# schematic.net
KiCad netlist of a schematic drawn in Altium Designer
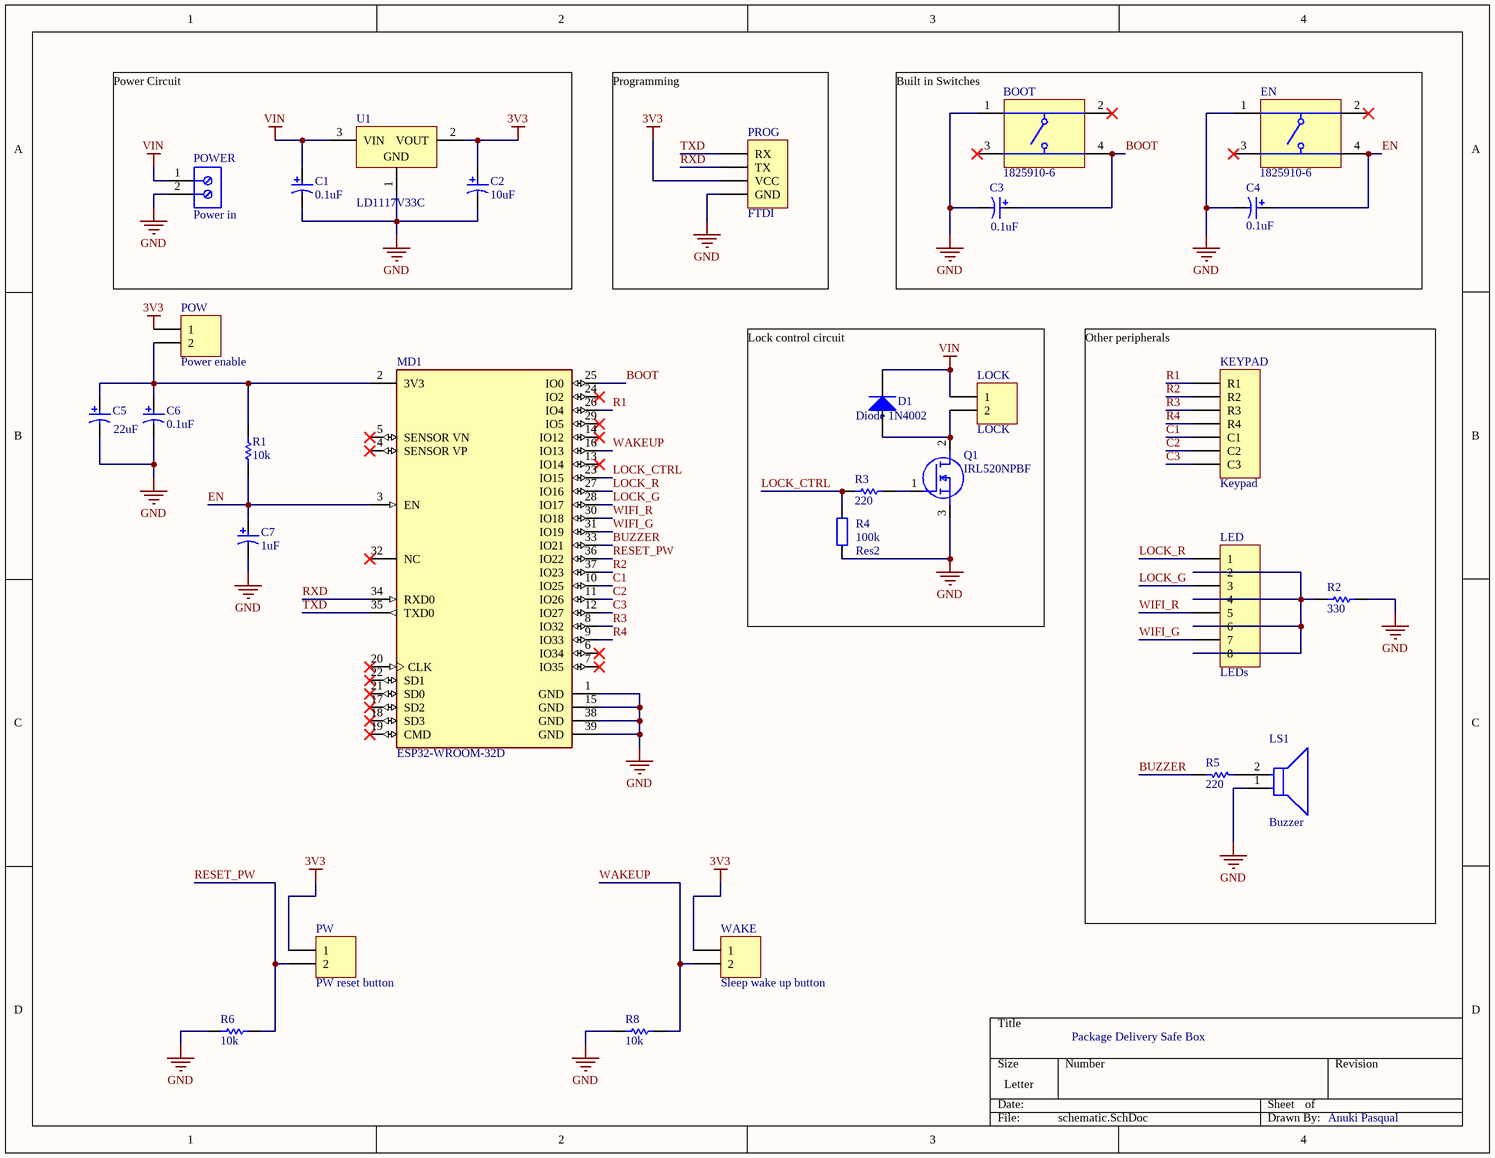
[diagram p0: schematic.SchDoc]

(export (version "E")
  (design (tool "Eeschema 10.0.6"))
  (components
    (comp (ref "BOOT")
      (value "1825910-6")
      (footprint "TECO-1825910-6_V")
      (description "Tact Switch, SPST-NO, 0.05 A, -35 to 85 degC, 4-Pin THD, RoHS, Bulk")
      (fields (field (name "MANUFACTURER") "TE Connectivity"))
      (libsource (lib "Altium Content Vault") (part "SW-SPST-4_A"))
    )
    (comp (ref "C1")
      (value "0.1uF")
      (footprint "CAPPR55-200-1100X500X1200")
      (description "Aluminum Electrolytic Capacitor, 22 uF, +/- 20%, 50 V, -40 to 85 degC, 2-Pin THD, RoHS, Bulk")
      (fields (field (name "VOLTAGE") "50V") (field (name "MANUFACTURER") "Panasonic"))
      (libsource (lib "Altium Content Vault") (part "CAP-P-2"))
    )
    (comp (ref "C2")
      (value "10uF")
      (footprint "CAPPR55-200-1100X500X1200")
      (description "Aluminum Electrolytic Capacitor, 22 uF, +/- 20%, 50 V, -40 to 85 degC, 2-Pin THD, RoHS, Bulk")
      (fields (field (name "VOLTAGE") "50V") (field (name "MANUFACTURER") "Panasonic"))
      (libsource (lib "Altium Content Vault") (part "CAP-P-2"))
    )
    (comp (ref "C3")
      (value "0.1uF")
      (footprint "CAPPR55-200-1100X500X1200")
      (description "Aluminum Electrolytic Capacitor, 22 uF, +/- 20%, 50 V, -40 to 85 degC, 2-Pin THD, RoHS, Bulk")
      (fields (field (name "VOLTAGE") "50V") (field (name "MANUFACTURER") "Panasonic"))
      (libsource (lib "Altium Content Vault") (part "CAP-P-2"))
    )
    (comp (ref "C4")
      (value "0.1uF")
      (footprint "CAPPR55-200-1100X500X1200")
      (description "Aluminum Electrolytic Capacitor, 22 uF, +/- 20%, 50 V, -40 to 85 degC, 2-Pin THD, RoHS, Bulk")
      (fields (field (name "VOLTAGE") "50V") (field (name "MANUFACTURER") "Panasonic"))
      (libsource (lib "Altium Content Vault") (part "CAP-P-2"))
    )
    (comp (ref "C5")
      (value "22uF")
      (footprint "CAPPR55-200-1100X500X1200")
      (description "Aluminum Electrolytic Capacitor, 22 uF, +/- 20%, 50 V, -40 to 85 degC, 2-Pin THD, RoHS, Bulk")
      (fields (field (name "VOLTAGE") "50V") (field (name "MANUFACTURER") "Panasonic"))
      (libsource (lib "Altium Content Vault") (part "CAP-P-2"))
    )
    (comp (ref "C6")
      (value "0.1uF")
      (footprint "CAPPR55-200-1100X500X1200")
      (description "Aluminum Electrolytic Capacitor, 22 uF, +/- 20%, 50 V, -40 to 85 degC, 2-Pin THD, RoHS, Bulk")
      (fields (field (name "VOLTAGE") "50V") (field (name "MANUFACTURER") "Panasonic"))
      (libsource (lib "Altium Content Vault") (part "CAP-P-2"))
    )
    (comp (ref "C7")
      (value "1uF")
      (footprint "CAPPR55-200-1100X500X1200")
      (description "Aluminum Electrolytic Capacitor, 22 uF, +/- 20%, 50 V, -40 to 85 degC, 2-Pin THD, RoHS, Bulk")
      (fields (field (name "VOLTAGE") "50V") (field (name "MANUFACTURER") "Panasonic"))
      (libsource (lib "Altium Content Vault") (part "CAP-P-2"))
    )
    (comp (ref "D1")
      (value "Diode 1N4002")
      (footprint "DO-41")
      (description "1 Amp General Purpose Rectifier")
      (fields (field (name "PUBLISHER") "Altium Limited"))
      (libsource (lib "Miscellaneous Devices") (part "Diode 1N4002"))
    )
    (comp (ref "EN")
      (value "1825910-6")
      (footprint "TECO-1825910-6_V")
      (description "Tact Switch, SPST-NO, 0.05 A, -35 to 85 degC, 4-Pin THD, RoHS, Bulk")
      (fields (field (name "MANUFACTURER") "TE Connectivity"))
      (libsource (lib "Altium Content Vault") (part "SW-SPST-4_A"))
    )
    (comp (ref "KEYPAD")
      (value "Keypad")
      (footprint "Miscellaneous Connectors:HDR1X7")
      (description "Header, 7-Pin")
      (fields (field (name "PUBLISHER") "Altium Limited"))
      (libsource (lib "Miscellaneous Connectors") (part "Header 7"))
    )
    (comp (ref "LED")
      (value "LEDs")
      (footprint "HDR1X8")
      (description "Header, 8-Pin")
      (fields (field (name "PUBLISHER") "Altium Limited"))
      (libsource (lib "Miscellaneous Connectors") (part "Header 8"))
    )
    (comp (ref "LOCK")
      (value "LOCK")
      (footprint "HDR1X2")
      (description "Header, 2-Pin")
      (fields (field (name "PUBLISHER") "Altium Limited"))
      (libsource (lib "Miscellaneous Connectors") (part "Header 2"))
    )
    (comp (ref "LS1")
      (value "Buzzer")
      (footprint "FP-MCKPX-G1203A-K4056-MFG")
      (description "MAGNETIC BUZZER AND TRANSDUCER - More Details")
      (fields
        (field (name "MANUFACTURER PART NUMBER") "MCKPX-G1203A-K4056")
        (field (name "MANUFACTURER") "Multicomp Pro")
      )
      (libsource (lib "Altium Content Vault") (part "1973c4b650225fd2ddacaff6b763965"))
    )
    (comp (ref "MD1")
      (value "ESP32-WROOM-32D")
      (footprint "FP-ESP32-WROOM-32D-MFG")
      (description "WIFI MODULE 32MBITS SPI FLASH")
      (fields
        (field (name "OCTOPART") "https://octopart.com/esp32-wroom-32d-espressif+systems-91040050")
        (field (name "MANUFACTURER") "Espressif Systems")
      )
      (libsource (lib "Altium Content Vault") (part "a031a76f8c27026a7a7f4657ff233a3"))
    )
    (comp (ref "POW")
      (value "Power enable")
      (footprint "HDR1X2")
      (description "Header, 2-Pin")
      (fields (field (name "PUBLISHER") "Altium Limited"))
      (libsource (lib "Miscellaneous Connectors") (part "Header 2"))
    )
    (comp (ref "POWER")
      (value "Power in")
      (footprint "691102710002")
      (description "Series 102 - 5.00 mm Horizontal Entry Modular with Pressure Clamp WR-TBL, 2 pin")
      (fields
        (field (name "MANUFACTURER") "Wurth Elektronik")
        (field (name "PART NUMBER") "691102710002")
        (field (name "PUBLISHER") "WurthElektronik")
      )
      (libsource (lib "Altium Content Vault") (part "WE-CN-1P-F-TB2"))
    )
    (comp (ref "PROG")
      (value "FTDI")
      (footprint "HDR1X4")
      (description "Header, 4-Pin")
      (fields (field (name "PUBLISHER") "Altium Limited"))
      (libsource (lib "Miscellaneous Connectors") (part "Header 4"))
    )
    (comp (ref "PW")
      (value "PW reset button")
      (footprint "HDR1X2")
      (description "Header, 2-Pin")
      (fields (field (name "PUBLISHER") "Altium Limited"))
      (libsource (lib "Miscellaneous Connectors") (part "Header 2"))
    )
    (comp (ref "Q1")
      (value "IRL520NPBF")
      (footprint "SamacSys:TO254P469X1042X1967-3P")
      (description "MOSFET (N-Channel)")
      (fields (field (name "MOUSER PART NUMBER") "942-IRL520NPBF"))
      (libsource (lib "SamacSys") (part "IRL520NPBF"))
    )
    (comp (ref "R1")
      (value "10k")
      (footprint "AXIAL-0.3")
      (description "Resistor")
      (fields (field (name "PUBLISHER") "Altium Limited"))
      (libsource (lib "Miscellaneous Devices") (part "Res1"))
    )
    (comp (ref "R2")
      (value "330")
      (footprint "AXIAL-0.3")
      (description "Resistor")
      (fields (field (name "PUBLISHER") "Altium Limited"))
      (libsource (lib "Miscellaneous Devices") (part "Res1"))
    )
    (comp (ref "R3")
      (value "220")
      (footprint "AXIAL-0.3")
      (description "Resistor")
      (fields (field (name "PUBLISHER") "Altium Limited"))
      (libsource (lib "Miscellaneous Devices") (part "Res1"))
    )
    (comp (ref "R4")
      (value "Res2")
      (footprint "AXIAL-0.4")
      (description "Resistor")
      (fields (field (name "ALTIUM_VALUE") "100k") (field (name "PUBLISHER") "Altium Limited"))
      (libsource (lib "Miscellaneous Devices") (part "Res2"))
    )
    (comp (ref "R5")
      (value "220")
      (footprint "AXIAL-0.3")
      (description "Resistor")
      (fields (field (name "PUBLISHER") "Altium Limited"))
      (libsource (lib "Miscellaneous Devices") (part "Res1"))
    )
    (comp (ref "R6")
      (value "10k")
      (footprint "AXIAL-0.3")
      (description "Resistor")
      (fields (field (name "PUBLISHER") "Altium Limited"))
      (libsource (lib "Miscellaneous Devices") (part "Res1"))
    )
    (comp (ref "R8")
      (value "10k")
      (footprint "AXIAL-0.3")
      (description "Resistor")
      (fields (field (name "PUBLISHER") "Altium Limited"))
      (libsource (lib "Miscellaneous Devices") (part "Res1"))
    )
    (comp (ref "U1")
      (value "LD1117V33C")
      (footprint "TO220")
      (description "Fixed Low Drop Positive Voltage Regulator, 3.3V, 3-Pin TO-220")
      (libsource (lib "Altium Content Vault") (part "PM-REG-LD1117V-SIL3"))
    )
    (comp (ref "WAKE")
      (value "Sleep wake up button")
      (footprint "HDR1X2")
      (description "Header, 2-Pin")
      (fields (field (name "PUBLISHER") "Altium Limited"))
      (libsource (lib "Miscellaneous Connectors") (part "Header 2"))
    )
  )
  (nets
    (net (code "1") (name "/BOOT") (class "Default")
      (node (ref "BOOT") (pin "4") (pinfunction "4_4") (pintype "passive"))
      (node (ref "C3") (pin "1") (pinfunction "1_1") (pintype "passive"))
      (node (ref "MD1") (pin "25") (pinfunction "IO0_25") (pintype "bidirectional"))
    )
    (net (code "2") (name "/BUZZER") (class "Default")
      (node (ref "MD1") (pin "33") (pinfunction "IO21_33") (pintype "bidirectional"))
      (node (ref "R5") (pin "1") (pinfunction "1_1") (pintype "passive"))
    )
    (net (code "3") (name "/C1") (class "Default")
      (node (ref "KEYPAD") (pin "5") (pinfunction "C1_5") (pintype "passive"))
      (node (ref "MD1") (pin "10") (pinfunction "IO25_10") (pintype "bidirectional"))
    )
    (net (code "4") (name "/C2") (class "Default")
      (node (ref "KEYPAD") (pin "6") (pinfunction "C2_6") (pintype "passive"))
      (node (ref "MD1") (pin "11") (pinfunction "IO26_11") (pintype "bidirectional"))
    )
    (net (code "5") (name "/C3") (class "Default")
      (node (ref "KEYPAD") (pin "7") (pinfunction "C3_7") (pintype "passive"))
      (node (ref "MD1") (pin "12") (pinfunction "IO27_12") (pintype "bidirectional"))
    )
    (net (code "6") (name "/EN") (class "Default")
      (node (ref "C4") (pin "1") (pinfunction "1_1") (pintype "passive"))
      (node (ref "C7") (pin "1") (pinfunction "1_1") (pintype "passive"))
      (node (ref "EN") (pin "4") (pinfunction "4_4") (pintype "passive"))
      (node (ref "MD1") (pin "3") (pinfunction "EN_3") (pintype "input"))
      (node (ref "R1") (pin "1") (pinfunction "1_1") (pintype "passive"))
    )
    (net (code "7") (name "/LOCK_CTRL") (class "Default")
      (node (ref "MD1") (pin "23") (pinfunction "IO15_23") (pintype "bidirectional"))
      (node (ref "R3") (pin "2") (pinfunction "2_2") (pintype "passive"))
      (node (ref "R4") (pin "2") (pinfunction "2_2") (pintype "passive"))
    )
    (net (code "8") (name "/LOCK_G") (class "Default")
      (node (ref "LED") (pin "3") (pinfunction "3_3") (pintype "passive"))
      (node (ref "MD1") (pin "28") (pinfunction "IO17_28") (pintype "bidirectional"))
    )
    (net (code "9") (name "/LOCK_R") (class "Default")
      (node (ref "LED") (pin "1") (pinfunction "1_1") (pintype "passive"))
      (node (ref "MD1") (pin "27") (pinfunction "IO16_27") (pintype "bidirectional"))
    )
    (net (code "10") (name "/R1") (class "Default")
      (node (ref "KEYPAD") (pin "1") (pinfunction "R1_1") (pintype "passive"))
      (node (ref "MD1") (pin "26") (pinfunction "IO4_26") (pintype "bidirectional"))
    )
    (net (code "11") (name "/R2") (class "Default")
      (node (ref "KEYPAD") (pin "2") (pinfunction "R2_2") (pintype "passive"))
      (node (ref "MD1") (pin "37") (pinfunction "IO23_37") (pintype "bidirectional"))
    )
    (net (code "12") (name "/R3") (class "Default")
      (node (ref "KEYPAD") (pin "3") (pinfunction "R3_3") (pintype "passive"))
      (node (ref "MD1") (pin "8") (pinfunction "IO32_8") (pintype "bidirectional"))
    )
    (net (code "13") (name "/R4") (class "Default")
      (node (ref "KEYPAD") (pin "4") (pinfunction "R4_4") (pintype "passive"))
      (node (ref "MD1") (pin "9") (pinfunction "IO33_9") (pintype "bidirectional"))
    )
    (net (code "14") (name "/RESET_PW") (class "Default")
      (node (ref "MD1") (pin "36") (pinfunction "IO22_36") (pintype "bidirectional"))
      (node (ref "PW") (pin "2") (pinfunction "2_2") (pintype "passive"))
      (node (ref "R6") (pin "1") (pinfunction "1_1") (pintype "passive"))
    )
    (net (code "15") (name "/RXD") (class "Default")
      (node (ref "MD1") (pin "34") (pinfunction "RXD0_34") (pintype "input"))
      (node (ref "PROG") (pin "2") (pinfunction "TX_2") (pintype "passive"))
    )
    (net (code "16") (name "/TXD") (class "Default")
      (node (ref "MD1") (pin "35") (pinfunction "TXD0_35") (pintype "output"))
      (node (ref "PROG") (pin "1") (pinfunction "RX_1") (pintype "passive"))
    )
    (net (code "17") (name "/WAKEUP") (class "Default")
      (node (ref "MD1") (pin "16") (pinfunction "IO13_16") (pintype "bidirectional"))
      (node (ref "R8") (pin "1") (pinfunction "1_1") (pintype "passive"))
      (node (ref "WAKE") (pin "2") (pinfunction "2_2") (pintype "passive"))
    )
    (net (code "18") (name "/WIFI_G") (class "Default")
      (node (ref "LED") (pin "7") (pinfunction "7_7") (pintype "passive"))
      (node (ref "MD1") (pin "31") (pinfunction "IO19_31") (pintype "bidirectional"))
    )
    (net (code "19") (name "/WIFI_R") (class "Default")
      (node (ref "LED") (pin "5") (pinfunction "5_5") (pintype "passive"))
      (node (ref "MD1") (pin "30") (pinfunction "IO18_30") (pintype "bidirectional"))
    )
    (net (code "20") (name "3V3") (class "Default")
      (node (ref "C2") (pin "1") (pinfunction "1_1") (pintype "passive"))
      (node (ref "POW") (pin "1") (pinfunction "1_1") (pintype "passive"))
      (node (ref "PROG") (pin "3") (pinfunction "VCC_3") (pintype "passive"))
      (node (ref "PW") (pin "1") (pinfunction "1_1") (pintype "passive"))
      (node (ref "U1") (pin "2") (pinfunction "VOUT_2") (pintype "power_in"))
      (node (ref "WAKE") (pin "1") (pinfunction "1_1") (pintype "passive"))
    )
    (net (code "21") (name "GND") (class "Default")
      (node (ref "BOOT") (pin "1") (pinfunction "1_1") (pintype "passive"))
      (node (ref "C1") (pin "2") (pinfunction "2_2") (pintype "passive"))
      (node (ref "C2") (pin "2") (pinfunction "2_2") (pintype "passive"))
      (node (ref "C3") (pin "2") (pinfunction "2_2") (pintype "passive"))
      (node (ref "C4") (pin "2") (pinfunction "2_2") (pintype "passive"))
      (node (ref "C5") (pin "2") (pinfunction "2_2") (pintype "passive"))
      (node (ref "C6") (pin "2") (pinfunction "2_2") (pintype "passive"))
      (node (ref "C7") (pin "2") (pinfunction "2_2") (pintype "passive"))
      (node (ref "EN") (pin "1") (pinfunction "1_1") (pintype "passive"))
      (node (ref "LS1") (pin "1") (pinfunction "C_1") (pintype "passive"))
      (node (ref "MD1") (pin "1") (pinfunction "GND_1") (pintype "power_in"))
      (node (ref "MD1") (pin "15") (pinfunction "GND_15") (pintype "power_in"))
      (node (ref "MD1") (pin "38") (pinfunction "GND_38") (pintype "power_in"))
      (node (ref "MD1") (pin "39") (pinfunction "GND_39") (pintype "power_in"))
      (node (ref "POWER") (pin "2") (pinfunction "2_2") (pintype "passive"))
      (node (ref "PROG") (pin "4") (pinfunction "GND_4") (pintype "passive"))
      (node (ref "Q1") (pin "3") (pinfunction "S_3") (pintype "passive"))
      (node (ref "R2") (pin "2") (pinfunction "2_2") (pintype "passive"))
      (node (ref "R4") (pin "1") (pinfunction "1_1") (pintype "passive"))
      (node (ref "R6") (pin "2") (pinfunction "2_2") (pintype "passive"))
      (node (ref "R8") (pin "2") (pinfunction "2_2") (pintype "passive"))
      (node (ref "U1") (pin "1") (pinfunction "GND_1") (pintype "power_in"))
    )
    (net (code "22") (name "Net-(D1-A)") (class "Default")
      (node (ref "D1") (pin "1") (pinfunction "A_1") (pintype "passive"))
      (node (ref "LOCK") (pin "2") (pinfunction "2_2") (pintype "passive"))
      (node (ref "Q1") (pin "2") (pinfunction "D_2") (pintype "passive"))
    )
    (net (code "23") (name "Net-(LED-Pad2)") (class "Default")
      (node (ref "LED") (pin "2") (pinfunction "2_2") (pintype "passive"))
      (node (ref "LED") (pin "4") (pinfunction "4_4") (pintype "passive"))
      (node (ref "LED") (pin "6") (pinfunction "6_6") (pintype "passive"))
      (node (ref "LED") (pin "8") (pinfunction "8_8") (pintype "passive"))
      (node (ref "R2") (pin "1") (pinfunction "1_1") (pintype "passive"))
    )
    (net (code "24") (name "Net-(LS1-A)") (class "Default")
      (node (ref "LS1") (pin "2") (pinfunction "A_2") (pintype "passive"))
      (node (ref "R5") (pin "2") (pinfunction "2_2") (pintype "passive"))
    )
    (net (code "25") (name "Net-(MD1-3V3)") (class "Default")
      (node (ref "C5") (pin "1") (pinfunction "1_1") (pintype "passive"))
      (node (ref "C6") (pin "1") (pinfunction "1_1") (pintype "passive"))
      (node (ref "MD1") (pin "2") (pinfunction "3V3_2") (pintype "power_in"))
      (node (ref "POW") (pin "2") (pinfunction "2_2") (pintype "passive"))
      (node (ref "R1") (pin "2") (pinfunction "2_2") (pintype "passive"))
    )
    (net (code "26") (name "Net-(Q1-G)") (class "Default")
      (node (ref "Q1") (pin "1") (pinfunction "G_1") (pintype "passive"))
      (node (ref "R3") (pin "1") (pinfunction "1_1") (pintype "passive"))
    )
    (net (code "27") (name "VIN") (class "Default")
      (node (ref "C1") (pin "1") (pinfunction "1_1") (pintype "passive"))
      (node (ref "D1") (pin "2") (pinfunction "K_2") (pintype "passive"))
      (node (ref "LOCK") (pin "1") (pinfunction "1_1") (pintype "passive"))
      (node (ref "POWER") (pin "1") (pinfunction "1_1") (pintype "passive"))
      (node (ref "U1") (pin "3") (pinfunction "VIN_3") (pintype "power_in"))
    )
    (net (code "28") (name "unconnected-(BOOT-Pad2)") (class "Default")
      (node (ref "BOOT") (pin "2") (pinfunction "2_2") (pintype "passive+no_connect"))
    )
    (net (code "29") (name "unconnected-(BOOT-Pad3)") (class "Default")
      (node (ref "BOOT") (pin "3") (pinfunction "3_3") (pintype "passive+no_connect"))
    )
    (net (code "30") (name "unconnected-(EN-Pad2)") (class "Default")
      (node (ref "EN") (pin "2") (pinfunction "2_2") (pintype "passive+no_connect"))
    )
    (net (code "31") (name "unconnected-(EN-Pad3)") (class "Default")
      (node (ref "EN") (pin "3") (pinfunction "3_3") (pintype "passive+no_connect"))
    )
    (net (code "32") (name "unconnected-(MD1-CLK-Pad20)") (class "Default")
      (node (ref "MD1") (pin "20") (pinfunction "CLK_20") (pintype "input+no_connect"))
    )
    (net (code "33") (name "unconnected-(MD1-CMD-Pad19)") (class "Default")
      (node (ref "MD1") (pin "19") (pinfunction "CMD_19") (pintype "bidirectional+no_connect"))
    )
    (net (code "34") (name "unconnected-(MD1-IO2-Pad24)") (class "Default")
      (node (ref "MD1") (pin "24") (pinfunction "IO2_24") (pintype "bidirectional+no_connect"))
    )
    (net (code "35") (name "unconnected-(MD1-IO5-Pad29)") (class "Default")
      (node (ref "MD1") (pin "29") (pinfunction "IO5_29") (pintype "bidirectional+no_connect"))
    )
    (net (code "36") (name "unconnected-(MD1-IO12-Pad14)") (class "Default")
      (node (ref "MD1") (pin "14") (pinfunction "IO12_14") (pintype "bidirectional+no_connect"))
    )
    (net (code "37") (name "unconnected-(MD1-IO14-Pad13)") (class "Default")
      (node (ref "MD1") (pin "13") (pinfunction "IO14_13") (pintype "bidirectional+no_connect"))
    )
    (net (code "38") (name "unconnected-(MD1-IO34-Pad6)") (class "Default")
      (node (ref "MD1") (pin "6") (pinfunction "IO34_6") (pintype "bidirectional+no_connect"))
    )
    (net (code "39") (name "unconnected-(MD1-IO35-Pad7)") (class "Default")
      (node (ref "MD1") (pin "7") (pinfunction "IO35_7") (pintype "bidirectional+no_connect"))
    )
    (net (code "40") (name "unconnected-(MD1-NC-Pad32)") (class "Default")
      (node (ref "MD1") (pin "32") (pinfunction "NC_32") (pintype "passive+no_connect"))
    )
    (net (code "41") (name "unconnected-(MD1-SD0-Pad21)") (class "Default")
      (node (ref "MD1") (pin "21") (pinfunction "SD0_21") (pintype "bidirectional+no_connect"))
    )
    (net (code "42") (name "unconnected-(MD1-SD1-Pad22)") (class "Default")
      (node (ref "MD1") (pin "22") (pinfunction "SD1_22") (pintype "bidirectional+no_connect"))
    )
    (net (code "43") (name "unconnected-(MD1-SD2-Pad17)") (class "Default")
      (node (ref "MD1") (pin "17") (pinfunction "SD2_17") (pintype "bidirectional+no_connect"))
    )
    (net (code "44") (name "unconnected-(MD1-SD3-Pad18)") (class "Default")
      (node (ref "MD1") (pin "18") (pinfunction "SD3_18") (pintype "bidirectional+no_connect"))
    )
    (net (code "45") (name "unconnected-(MD1-SENSOR_VN-Pad5)") (class "Default")
      (node (ref "MD1") (pin "5") (pinfunction "SENSOR_VN_5") (pintype "bidirectional+no_connect"))
    )
    (net (code "46") (name "unconnected-(MD1-SENSOR_VP-Pad4)") (class "Default")
      (node (ref "MD1") (pin "4") (pinfunction "SENSOR_VP_4") (pintype "bidirectional+no_connect"))
    )
  )
)
